# Input-Connectors.net
KiCad netlist of a schematic drawn in Altium Designer
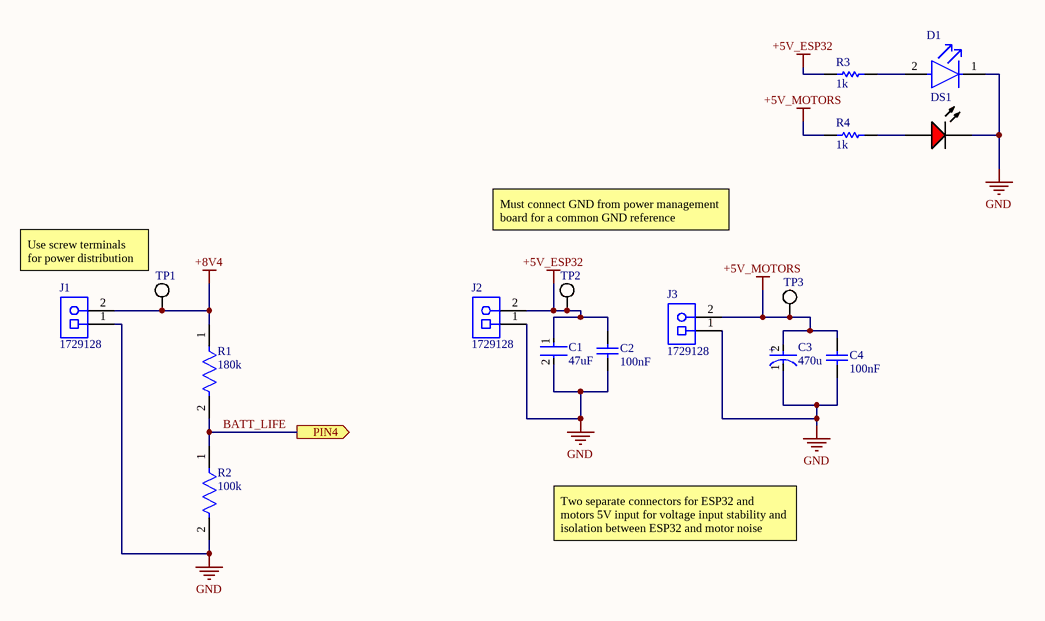
[diagram p0: Input-Connectors.SchDoc]

(export (version "E")
  (design (tool "Eeschema 10.0.6"))
  (components
    (comp (ref "C1")
      (value "47uF")
      (footprint "FP-CL32-IPC_C")
      (description "Cap Ceramic 47uF 16V X5R ±20% SMD 1210 +85°C Embossed T/R; CL32A476MOJNNWE")
      (libsource (lib "Altium Content Vault") (part "b4654b650e69147ec39a6b967a45e02"))
    )
    (comp (ref "C2")
      (value "100nF")
      (footprint "CAPC1206(3216)170_L")
      (description "CAP 100nF 50V ±10% 1206 (3216 Metric) Thickness 1.7mm SMD")
      (fields (field (name "TOLERANCE") "Â±10%"))
      (libsource (lib "Altium Content Vault") (part "CAP"))
    )
    (comp (ref "C3")
      (value "470u")
      (footprint "FP-RAD-TH-D_10_0_5-L_12_5-MFG")
      (description "Aluminum Electrolytic Capacitors (Radial Lead Type) 470uF ±20% 16V")
      (fields (field (name "TOLERANCE") "20%"))
      (libsource (lib "Altium Content Vault") (part "203bc49f2ac43e59fd269a8c329ed05"))
    )
    (comp (ref "C4")
      (value "100nF")
      (footprint "CAPC1206(3216)170_L")
      (description "CAP 100nF 50V ±10% 1206 (3216 Metric) Thickness 1.7mm SMD")
      (fields (field (name "TOLERANCE") "Â±10%"))
      (libsource (lib "Altium Content Vault") (part "CAP"))
    )
    (comp (ref "D1")
      (value "598-8270-107F")
      (footprint "FP-598-8270-107F-MFG")
      (description "SM LED 1206 ALINGAP G 7 REEL")
      (libsource (lib "Altium Content Vault") (part "8706943c75ba83719d021d2fdc84c58"))
    )
    (comp (ref "DS1")
      (value "SML-LX1206IC-TR")
      (footprint "LUMX-SML-LX1206IC_V")
      (description "LED Red, 65 mW, -40 to 85 degC, 2-Pin SMD, RoHS, Tape and Reel")
      (fields (field (name "MANUFACTURER") "Lumex"))
      (libsource (lib "Altium Content Vault") (part "LED-RED-AK-2"))
    )
    (comp (ref "J1")
      (value "1729128")
      (footprint "PHOE-1729128-2_V")
      (description "PCB Terminal Block, 13.5 A, 400 V, 2-Pin THD, RoHS, Bulk")
      (fields (field (name "MANUFACTURER") "Phoenix Contact"))
      (libsource (lib "Altium Content Vault") (part "CN-2P-F-R2"))
    )
    (comp (ref "J2")
      (value "1729128")
      (footprint "PHOE-1729128-2_V")
      (description "PCB Terminal Block, 13.5 A, 400 V, 2-Pin THD, RoHS, Bulk")
      (fields (field (name "MANUFACTURER") "Phoenix Contact"))
      (libsource (lib "Altium Content Vault") (part "CN-2P-F-R2"))
    )
    (comp (ref "J3")
      (value "1729128")
      (footprint "PHOE-1729128-2_V")
      (description "PCB Terminal Block, 13.5 A, 400 V, 2-Pin THD, RoHS, Bulk")
      (fields (field (name "MANUFACTURER") "Phoenix Contact"))
      (libsource (lib "Altium Content Vault") (part "CN-2P-F-R2"))
    )
    (comp (ref "R1")
      (value "180k")
      (footprint "FP-CRCW1206-e3-IPC_B")
      (description "RES Thick Film, 180kΩ, 5%, 0.25W, 200ppm/°C, 1206")
      (fields (field (name "TOLERANCE") "5%"))
      (libsource (lib "Altium Content Vault") (part "1029c3af85768c4190bb7ad29bc67b5"))
    )
    (comp (ref "R2")
      (value "100k")
      (footprint "FP-RP732B-MFG")
      (description "Res Thin Film 1206 100KΩ 0.1% 0.25W 15ppm/°C Molded SMD")
      (fields
        (field (name "TOLERANCE") "0.1%")
        (field (name "OCTOPART") "https://octopart.com/rp73d2b100kbtg-te+connectivity-42012337")
      )
      (libsource (lib "Altium Content Vault") (part "1029c3af85768c4190bb7ad29bc67b5"))
    )
    (comp (ref "R3")
      (value "1k")
      (footprint "RESC3216X60X45ML10T20")
      (fields (field (name "MANUFACTURER") "Vishay Dale") (field (name "PART NUMBER") "CRCW12061K00JNTA"))
      (libsource (lib "Altium Content Vault") (part "RES"))
    )
    (comp (ref "R4")
      (value "1k")
      (footprint "RESC3216X60X45ML10T20")
      (fields (field (name "MANUFACTURER") "Vishay Dale") (field (name "PART NUMBER") "CRCW12061K00JNTA"))
      (libsource (lib "Altium Content Vault") (part "RES"))
    )
    (comp (ref "TP1")
      (value "Test Point")
      (footprint "Test Point")
      (libsource (lib "University of California, Riverside") (part "Test Point"))
    )
    (comp (ref "TP2")
      (value "Test Point")
      (footprint "Test Point")
      (libsource (lib "University of California, Riverside") (part "Test Point"))
    )
    (comp (ref "TP3")
      (value "Test Point")
      (footprint "Test Point")
      (libsource (lib "University of California, Riverside") (part "Test Point"))
    )
  )
  (nets
    (net (code "1") (name "+5V_ESP32") (class "Default")
      (node (ref "C1") (pin "1") (pinfunction "1_1") (pintype "passive"))
      (node (ref "C2") (pin "2") (pinfunction "2_2") (pintype "passive"))
      (node (ref "J2") (pin "2") (pinfunction "2_2") (pintype "passive"))
      (node (ref "R3") (pin "1") (pinfunction "1_1") (pintype "passive"))
      (node (ref "TP2") (pin "1") (pinfunction "1_1") (pintype "passive"))
    )
    (net (code "2") (name "+5V_MOTORS") (class "Default")
      (node (ref "C3") (pin "2") (pinfunction "A_2") (pintype "passive"))
      (node (ref "C4") (pin "2") (pinfunction "2_2") (pintype "passive"))
      (node (ref "J3") (pin "2") (pinfunction "2_2") (pintype "passive"))
      (node (ref "R4") (pin "1") (pinfunction "1_1") (pintype "passive"))
      (node (ref "TP3") (pin "1") (pinfunction "1_1") (pintype "passive"))
    )
    (net (code "3") (name "+8V4") (class "Default")
      (node (ref "J1") (pin "2") (pinfunction "2_2") (pintype "passive"))
      (node (ref "R1") (pin "1") (pinfunction "1_1") (pintype "passive"))
      (node (ref "TP1") (pin "1") (pinfunction "1_1") (pintype "passive"))
    )
    (net (code "4") (name "/BATT_LIFE") (class "Default")
      (node (ref "R1") (pin "2") (pinfunction "2_2") (pintype "passive"))
      (node (ref "R2") (pin "1") (pinfunction "1_1") (pintype "passive"))
    )
    (net (code "5") (name "GND") (class "Default")
      (node (ref "C1") (pin "2") (pinfunction "2_2") (pintype "passive"))
      (node (ref "C2") (pin "1") (pinfunction "1_1") (pintype "passive"))
      (node (ref "C3") (pin "1") (pinfunction "C_1") (pintype "passive"))
      (node (ref "C4") (pin "1") (pinfunction "1_1") (pintype "passive"))
      (node (ref "D1") (pin "1") (pinfunction "C_1") (pintype "passive"))
      (node (ref "DS1") (pin "2") (pinfunction "K_2") (pintype "passive"))
      (node (ref "J1") (pin "1") (pinfunction "1_1") (pintype "passive"))
      (node (ref "J2") (pin "1") (pinfunction "1_1") (pintype "passive"))
      (node (ref "J3") (pin "1") (pinfunction "1_1") (pintype "passive"))
      (node (ref "R2") (pin "2") (pinfunction "2_2") (pintype "passive"))
    )
    (net (code "6") (name "Net-(D1-A)") (class "Default")
      (node (ref "D1") (pin "2") (pinfunction "A_2") (pintype "passive"))
      (node (ref "R3") (pin "2") (pinfunction "2_2") (pintype "passive"))
    )
    (net (code "7") (name "Net-(DS1-A)") (class "Default")
      (node (ref "DS1") (pin "1") (pinfunction "A_1") (pintype "passive"))
      (node (ref "R4") (pin "2") (pinfunction "2_2") (pintype "passive"))
    )
  )
)
